# PA_Encoder.net
KiCad netlist of a schematic drawn in Altium Designer
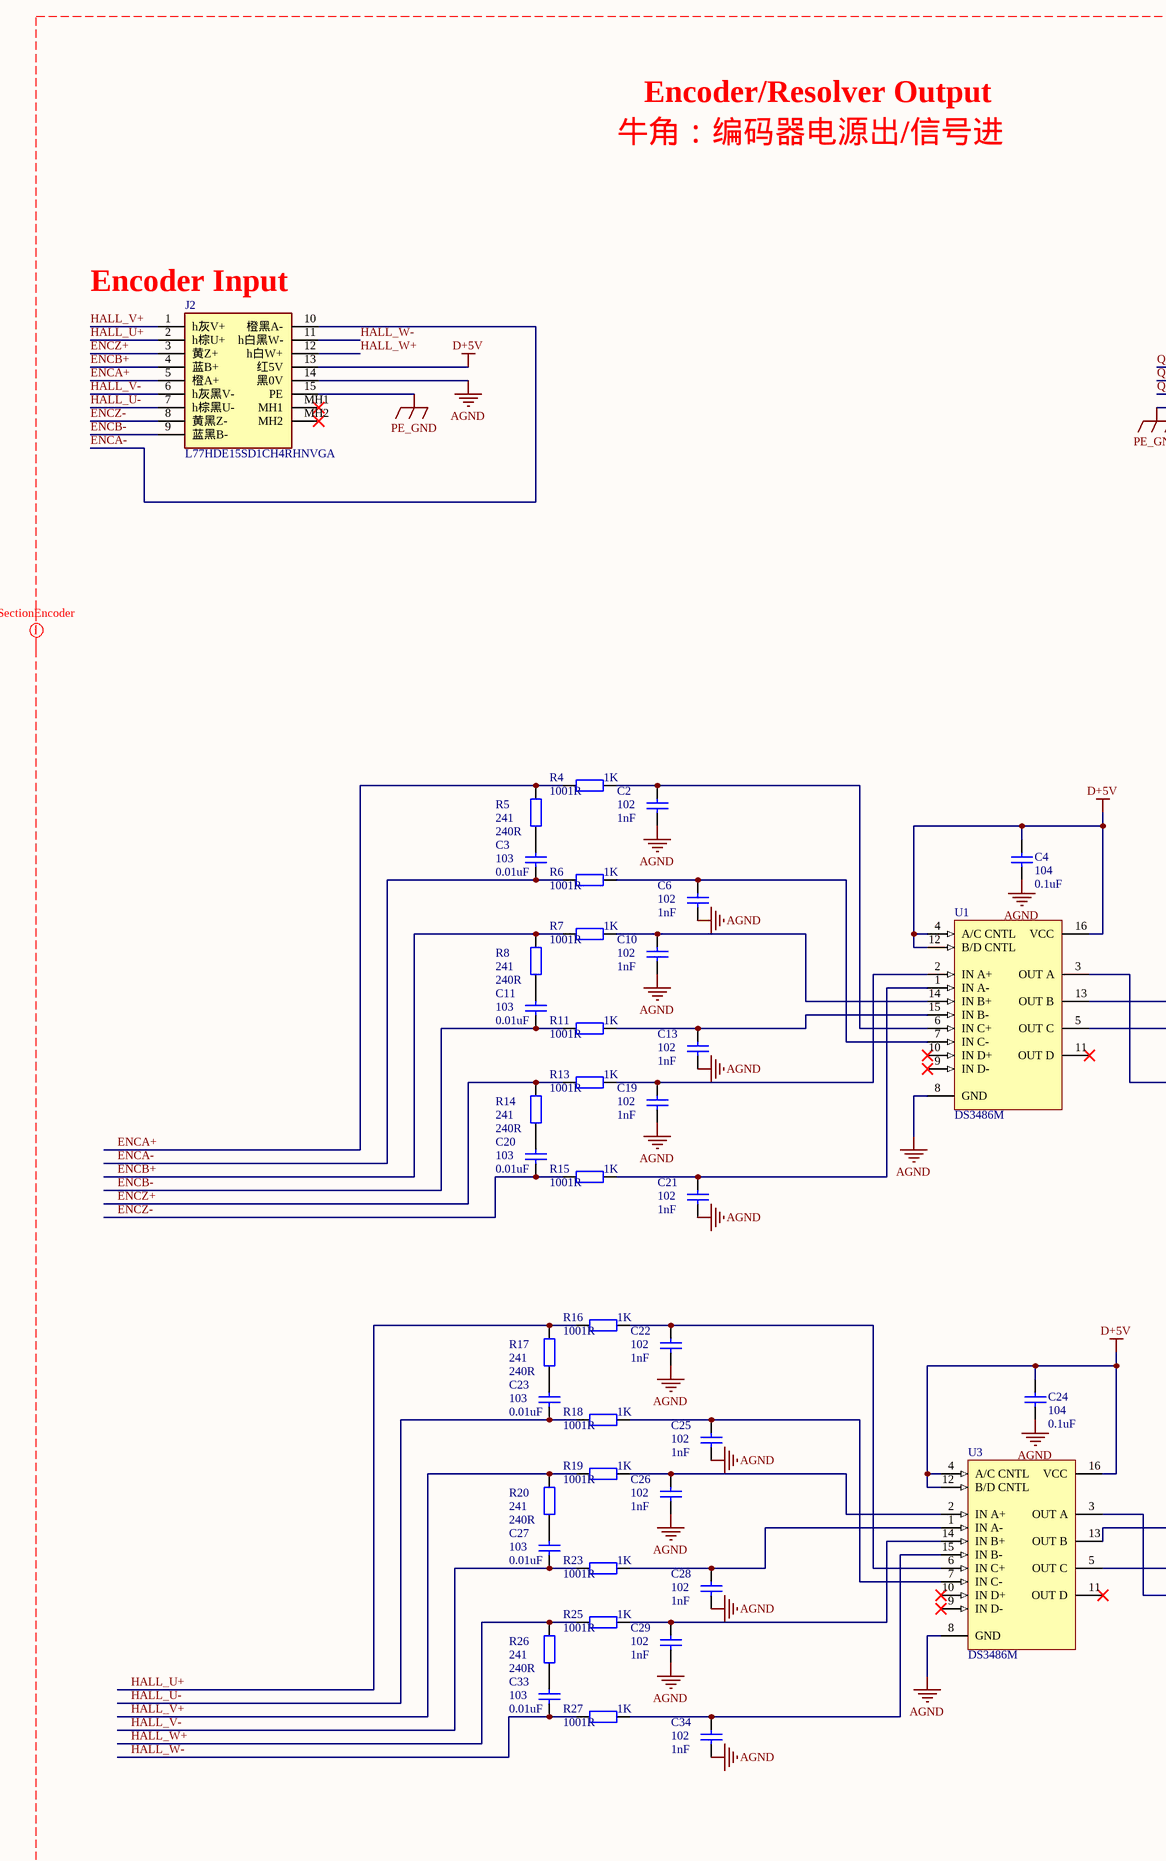
[diagram p0: PA_Encoder.SchDoc, left]
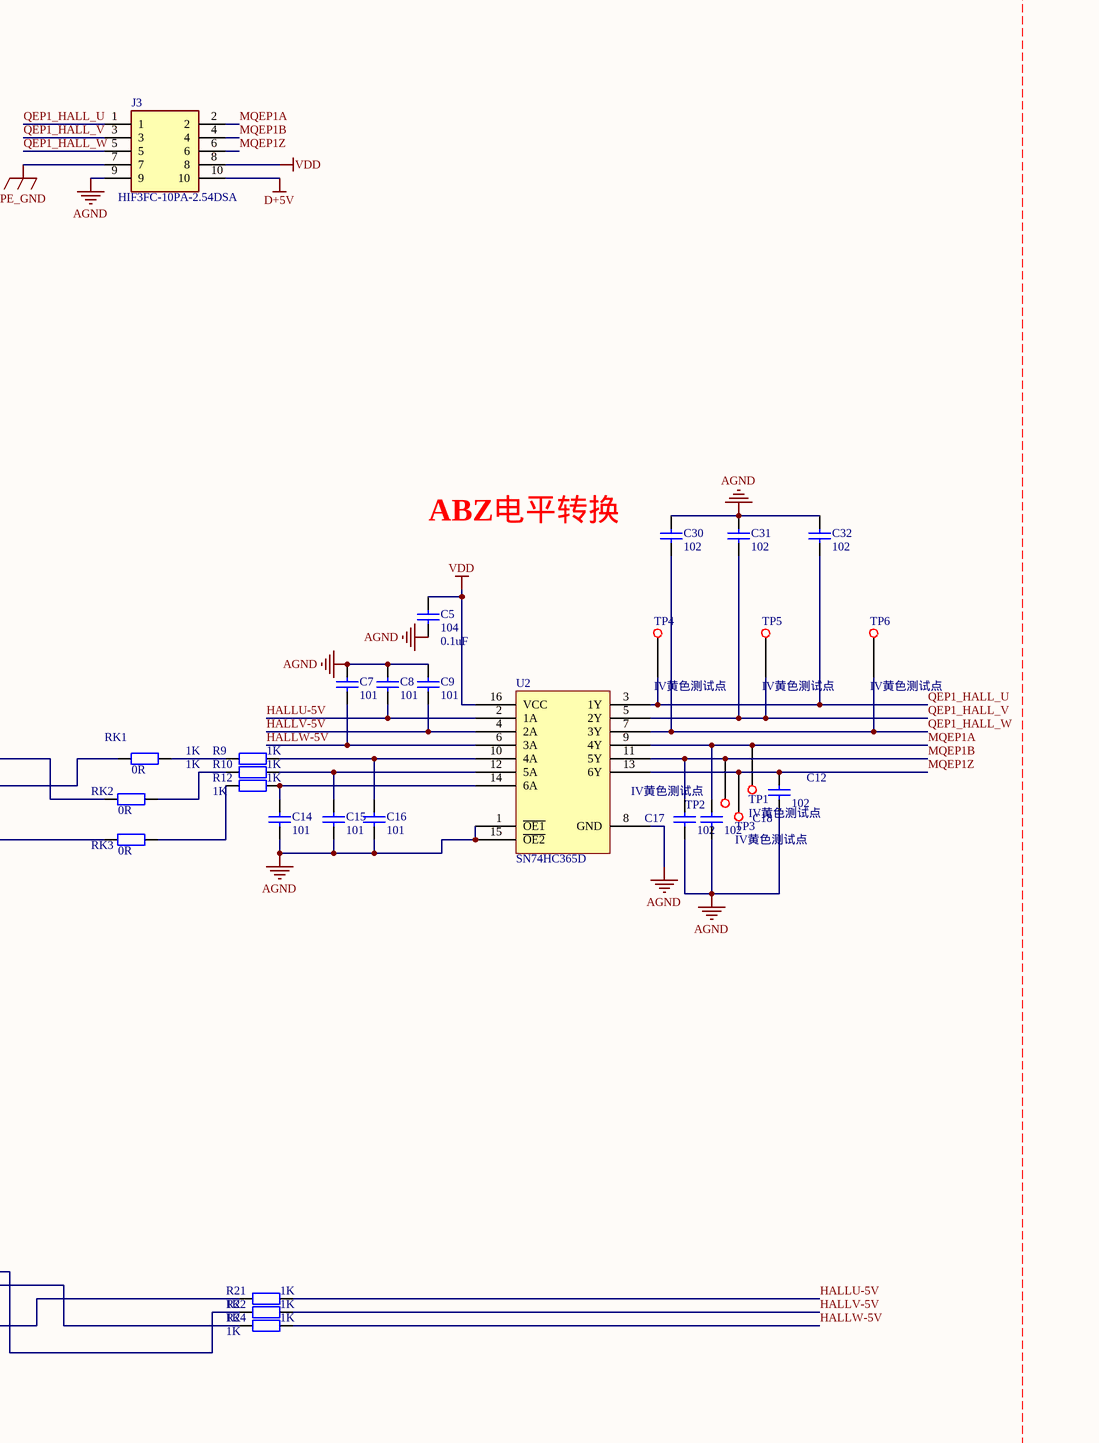
[diagram p1: PA_Encoder.SchDoc, middle]

(export (version "E")
  (design (tool "Eeschema 10.0.6"))
  (components
    (comp (ref "C2")
      (value "102")
      (footprint "0805")
      (description "Capacitor")
      (fields (field (name "ALTIUM_VALUE") "1nF") (field (name "PUBLISHER") "Altium Limited"))
      (libsource (lib "Miscellaneous Devices") (part "Cap"))
    )
    (comp (ref "C3")
      (value "103")
      (footprint "0805")
      (description "Capacitor")
      (fields (field (name "ALTIUM_VALUE") "0.01uF") (field (name "PUBLISHER") "Altium Limited"))
      (libsource (lib "Miscellaneous Devices") (part "Cap"))
    )
    (comp (ref "C4")
      (value "104")
      (footprint "0805")
      (description "Capacitor")
      (fields (field (name "ALTIUM_VALUE") "0.1uF") (field (name "PUBLISHER") "Altium Limited"))
      (libsource (lib "Miscellaneous Devices") (part "Cap"))
    )
    (comp (ref "C5")
      (value "104")
      (footprint "0805")
      (description "Capacitor")
      (fields (field (name "ALTIUM_VALUE") "0.1uF") (field (name "PUBLISHER") "Altium Limited"))
      (libsource (lib "Miscellaneous Devices") (part "Cap"))
    )
    (comp (ref "C6")
      (value "102")
      (footprint "0805")
      (description "Capacitor")
      (fields (field (name "ALTIUM_VALUE") "1nF") (field (name "PUBLISHER") "Altium Limited"))
      (libsource (lib "Miscellaneous Devices") (part "Cap"))
    )
    (comp (ref "C7")
      (value "101")
      (footprint "0805")
      (description "Capacitor")
      (fields (field (name "PUBLISHER") "Altium Limited"))
      (libsource (lib "Miscellaneous Devices") (part "Cap"))
    )
    (comp (ref "C8")
      (value "101")
      (footprint "0805")
      (description "Capacitor")
      (fields (field (name "PUBLISHER") "Altium Limited"))
      (libsource (lib "Miscellaneous Devices") (part "Cap"))
    )
    (comp (ref "C9")
      (value "101")
      (footprint "0805")
      (description "Capacitor")
      (fields (field (name "PUBLISHER") "Altium Limited"))
      (libsource (lib "Miscellaneous Devices") (part "Cap"))
    )
    (comp (ref "C10")
      (value "102")
      (footprint "0805")
      (description "Capacitor")
      (fields (field (name "ALTIUM_VALUE") "1nF") (field (name "PUBLISHER") "Altium Limited"))
      (libsource (lib "Miscellaneous Devices") (part "Cap"))
    )
    (comp (ref "C11")
      (value "103")
      (footprint "0805")
      (description "Capacitor")
      (fields (field (name "ALTIUM_VALUE") "0.01uF") (field (name "PUBLISHER") "Altium Limited"))
      (libsource (lib "Miscellaneous Devices") (part "Cap"))
    )
    (comp (ref "C12")
      (value "102")
      (footprint "0805")
      (description "Capacitor")
      (fields (field (name "PUBLISHER") "Altium Limited"))
      (libsource (lib "Miscellaneous Devices") (part "Cap"))
    )
    (comp (ref "C13")
      (value "102")
      (footprint "0805")
      (description "Capacitor")
      (fields (field (name "ALTIUM_VALUE") "1nF") (field (name "PUBLISHER") "Altium Limited"))
      (libsource (lib "Miscellaneous Devices") (part "Cap"))
    )
    (comp (ref "C14")
      (value "101")
      (footprint "0805")
      (description "Capacitor")
      (fields (field (name "PUBLISHER") "Altium Limited"))
      (libsource (lib "Miscellaneous Devices") (part "Cap"))
    )
    (comp (ref "C15")
      (value "101")
      (footprint "0805")
      (description "Capacitor")
      (fields (field (name "PUBLISHER") "Altium Limited"))
      (libsource (lib "Miscellaneous Devices") (part "Cap"))
    )
    (comp (ref "C16")
      (value "101")
      (footprint "0805")
      (description "Capacitor")
      (fields (field (name "PUBLISHER") "Altium Limited"))
      (libsource (lib "Miscellaneous Devices") (part "Cap"))
    )
    (comp (ref "C17")
      (value "102")
      (footprint "0805")
      (description "Capacitor")
      (fields (field (name "PUBLISHER") "Altium Limited"))
      (libsource (lib "Miscellaneous Devices") (part "Cap"))
    )
    (comp (ref "C18")
      (value "102")
      (footprint "0805")
      (description "Capacitor")
      (fields (field (name "PUBLISHER") "Altium Limited"))
      (libsource (lib "Miscellaneous Devices") (part "Cap"))
    )
    (comp (ref "C19")
      (value "102")
      (footprint "0805")
      (description "Capacitor")
      (fields (field (name "ALTIUM_VALUE") "1nF") (field (name "PUBLISHER") "Altium Limited"))
      (libsource (lib "Miscellaneous Devices") (part "Cap"))
    )
    (comp (ref "C20")
      (value "103")
      (footprint "0805")
      (description "Capacitor")
      (fields (field (name "ALTIUM_VALUE") "0.01uF") (field (name "PUBLISHER") "Altium Limited"))
      (libsource (lib "Miscellaneous Devices") (part "Cap"))
    )
    (comp (ref "C21")
      (value "102")
      (footprint "0805")
      (description "Capacitor")
      (fields (field (name "ALTIUM_VALUE") "1nF") (field (name "PUBLISHER") "Altium Limited"))
      (libsource (lib "Miscellaneous Devices") (part "Cap"))
    )
    (comp (ref "C22")
      (value "102")
      (footprint "0805")
      (description "Capacitor")
      (fields (field (name "ALTIUM_VALUE") "1nF") (field (name "PUBLISHER") "Altium Limited"))
      (libsource (lib "Miscellaneous Devices") (part "Cap"))
    )
    (comp (ref "C23")
      (value "103")
      (footprint "0805")
      (description "Capacitor")
      (fields (field (name "ALTIUM_VALUE") "0.01uF") (field (name "PUBLISHER") "Altium Limited"))
      (libsource (lib "Miscellaneous Devices") (part "Cap"))
    )
    (comp (ref "C24")
      (value "104")
      (footprint "0805")
      (description "Capacitor")
      (fields (field (name "ALTIUM_VALUE") "0.1uF") (field (name "PUBLISHER") "Altium Limited"))
      (libsource (lib "Miscellaneous Devices") (part "Cap"))
    )
    (comp (ref "C25")
      (value "102")
      (footprint "0805")
      (description "Capacitor")
      (fields (field (name "ALTIUM_VALUE") "1nF") (field (name "PUBLISHER") "Altium Limited"))
      (libsource (lib "Miscellaneous Devices") (part "Cap"))
    )
    (comp (ref "C26")
      (value "102")
      (footprint "0805")
      (description "Capacitor")
      (fields (field (name "ALTIUM_VALUE") "1nF") (field (name "PUBLISHER") "Altium Limited"))
      (libsource (lib "Miscellaneous Devices") (part "Cap"))
    )
    (comp (ref "C27")
      (value "103")
      (footprint "0805")
      (description "Capacitor")
      (fields (field (name "ALTIUM_VALUE") "0.01uF") (field (name "PUBLISHER") "Altium Limited"))
      (libsource (lib "Miscellaneous Devices") (part "Cap"))
    )
    (comp (ref "C28")
      (value "102")
      (footprint "0805")
      (description "Capacitor")
      (fields (field (name "ALTIUM_VALUE") "1nF") (field (name "PUBLISHER") "Altium Limited"))
      (libsource (lib "Miscellaneous Devices") (part "Cap"))
    )
    (comp (ref "C29")
      (value "102")
      (footprint "0805")
      (description "Capacitor")
      (fields (field (name "ALTIUM_VALUE") "1nF") (field (name "PUBLISHER") "Altium Limited"))
      (libsource (lib "Miscellaneous Devices") (part "Cap"))
    )
    (comp (ref "C30")
      (value "102")
      (footprint "0805")
      (description "Capacitor")
      (fields (field (name "PUBLISHER") "Altium Limited"))
      (libsource (lib "Miscellaneous Devices") (part "Cap"))
    )
    (comp (ref "C31")
      (value "102")
      (footprint "0805")
      (description "Capacitor")
      (fields (field (name "PUBLISHER") "Altium Limited"))
      (libsource (lib "Miscellaneous Devices") (part "Cap"))
    )
    (comp (ref "C32")
      (value "102")
      (footprint "0805")
      (description "Capacitor")
      (fields (field (name "PUBLISHER") "Altium Limited"))
      (libsource (lib "Miscellaneous Devices") (part "Cap"))
    )
    (comp (ref "C33")
      (value "103")
      (footprint "0805")
      (description "Capacitor")
      (fields (field (name "ALTIUM_VALUE") "0.01uF") (field (name "PUBLISHER") "Altium Limited"))
      (libsource (lib "Miscellaneous Devices") (part "Cap"))
    )
    (comp (ref "C34")
      (value "102")
      (footprint "0805")
      (description "Capacitor")
      (fields (field (name "ALTIUM_VALUE") "1nF") (field (name "PUBLISHER") "Altium Limited"))
      (libsource (lib "Miscellaneous Devices") (part "Cap"))
    )
    (comp (ref "J2")
      (value "L77HDE15SD1CH4RHNVGA")
      (footprint "L77hde15sd1ch4rhnvga")
      (description "Connector")
      (fields (field (name "MOUSER PART NUMBER") "523-7HDE15SDH4RHNVGA"))
      (libsource (lib "Project_Arsene") (part "VGA_母头_时代超群15线编码器定义"))
    )
    (comp (ref "J3")
      (value "HIF3FC-10PA-2.54DSA")
      (footprint "HIF3FC-10PA-2.54DSA")
      (description "Connector")
      (fields
        (field (name "MANUFACTURER_PART_NUMBER") "HIF3FC-10PA-2.54DSA(71)")
        (field (name "MOUSER PART NUMBER") "798-HIF3FC10PA254D71")
      )
      (libsource (lib "Project_Arsene") (part "HIF3FC-10PA-2.54DSA"))
    )
    (comp (ref "R4")
      (value "1001R")
      (footprint "0805")
      (description "Resistor")
      (fields (field (name "ALTIUM_VALUE") "1K") (field (name "PUBLISHER") "Altium Limited"))
      (libsource (lib "Miscellaneous Devices") (part "Res2"))
    )
    (comp (ref "R5")
      (value "241")
      (footprint "0805")
      (description "Resistor")
      (fields (field (name "ALTIUM_VALUE") "240R") (field (name "PUBLISHER") "Altium Limited"))
      (libsource (lib "") (part "Res2_1"))
    )
    (comp (ref "R6")
      (value "1001R")
      (footprint "0805")
      (description "Resistor")
      (fields (field (name "ALTIUM_VALUE") "1K") (field (name "PUBLISHER") "Altium Limited"))
      (libsource (lib "Miscellaneous Devices") (part "Res2"))
    )
    (comp (ref "R7")
      (value "1001R")
      (footprint "0805")
      (description "Resistor")
      (fields (field (name "ALTIUM_VALUE") "1K") (field (name "PUBLISHER") "Altium Limited"))
      (libsource (lib "Miscellaneous Devices") (part "Res2"))
    )
    (comp (ref "R8")
      (value "241")
      (footprint "0805")
      (description "Resistor")
      (fields (field (name "ALTIUM_VALUE") "240R") (field (name "PUBLISHER") "Altium Limited"))
      (libsource (lib "") (part "Res2_1"))
    )
    (comp (ref "R9")
      (value "1K")
      (footprint "0805")
      (description "Resistor")
      (fields (field (name "ALTIUM_VALUE") "1K") (field (name "PUBLISHER") "Altium Limited"))
      (libsource (lib "Miscellaneous Devices") (part "Res2"))
    )
    (comp (ref "R10")
      (value "1K")
      (footprint "0805")
      (description "Resistor")
      (fields (field (name "ALTIUM_VALUE") "1K") (field (name "PUBLISHER") "Altium Limited"))
      (libsource (lib "Miscellaneous Devices") (part "Res2"))
    )
    (comp (ref "R11")
      (value "1001R")
      (footprint "0805")
      (description "Resistor")
      (fields (field (name "ALTIUM_VALUE") "1K") (field (name "PUBLISHER") "Altium Limited"))
      (libsource (lib "Miscellaneous Devices") (part "Res2"))
    )
    (comp (ref "R12")
      (value "1K")
      (footprint "0805")
      (description "Resistor")
      (fields (field (name "ALTIUM_VALUE") "1K") (field (name "PUBLISHER") "Altium Limited"))
      (libsource (lib "Miscellaneous Devices") (part "Res2"))
    )
    (comp (ref "R13")
      (value "1001R")
      (footprint "0805")
      (description "Resistor")
      (fields (field (name "ALTIUM_VALUE") "1K") (field (name "PUBLISHER") "Altium Limited"))
      (libsource (lib "Miscellaneous Devices") (part "Res2"))
    )
    (comp (ref "R14")
      (value "241")
      (footprint "0805")
      (description "Resistor")
      (fields (field (name "ALTIUM_VALUE") "240R") (field (name "PUBLISHER") "Altium Limited"))
      (libsource (lib "") (part "Res2_1"))
    )
    (comp (ref "R15")
      (value "1001R")
      (footprint "0805")
      (description "Resistor")
      (fields (field (name "ALTIUM_VALUE") "1K") (field (name "PUBLISHER") "Altium Limited"))
      (libsource (lib "Miscellaneous Devices") (part "Res2"))
    )
    (comp (ref "R16")
      (value "1001R")
      (footprint "0805")
      (description "Resistor")
      (fields (field (name "ALTIUM_VALUE") "1K") (field (name "PUBLISHER") "Altium Limited"))
      (libsource (lib "Miscellaneous Devices") (part "Res2"))
    )
    (comp (ref "R17")
      (value "241")
      (footprint "0805")
      (description "Resistor")
      (fields (field (name "ALTIUM_VALUE") "240R") (field (name "PUBLISHER") "Altium Limited"))
      (libsource (lib "") (part "Res2_1"))
    )
    (comp (ref "R18")
      (value "1001R")
      (footprint "0805")
      (description "Resistor")
      (fields (field (name "ALTIUM_VALUE") "1K") (field (name "PUBLISHER") "Altium Limited"))
      (libsource (lib "Miscellaneous Devices") (part "Res2"))
    )
    (comp (ref "R19")
      (value "1001R")
      (footprint "0805")
      (description "Resistor")
      (fields (field (name "ALTIUM_VALUE") "1K") (field (name "PUBLISHER") "Altium Limited"))
      (libsource (lib "Miscellaneous Devices") (part "Res2"))
    )
    (comp (ref "R20")
      (value "241")
      (footprint "0805")
      (description "Resistor")
      (fields (field (name "ALTIUM_VALUE") "240R") (field (name "PUBLISHER") "Altium Limited"))
      (libsource (lib "") (part "Res2_1"))
    )
    (comp (ref "R21")
      (value "1K")
      (footprint "0805")
      (description "Resistor")
      (fields (field (name "ALTIUM_VALUE") "1K") (field (name "PUBLISHER") "Altium Limited"))
      (libsource (lib "Miscellaneous Devices") (part "Res2"))
    )
    (comp (ref "R22")
      (value "1K")
      (footprint "0805")
      (description "Resistor")
      (fields (field (name "ALTIUM_VALUE") "1K") (field (name "PUBLISHER") "Altium Limited"))
      (libsource (lib "Miscellaneous Devices") (part "Res2"))
    )
    (comp (ref "R23")
      (value "1001R")
      (footprint "0805")
      (description "Resistor")
      (fields (field (name "ALTIUM_VALUE") "1K") (field (name "PUBLISHER") "Altium Limited"))
      (libsource (lib "Miscellaneous Devices") (part "Res2"))
    )
    (comp (ref "R24")
      (value "1K")
      (footprint "0805")
      (description "Resistor")
      (fields (field (name "ALTIUM_VALUE") "1K") (field (name "PUBLISHER") "Altium Limited"))
      (libsource (lib "Miscellaneous Devices") (part "Res2"))
    )
    (comp (ref "R25")
      (value "1001R")
      (footprint "0805")
      (description "Resistor")
      (fields (field (name "ALTIUM_VALUE") "1K") (field (name "PUBLISHER") "Altium Limited"))
      (libsource (lib "Miscellaneous Devices") (part "Res2"))
    )
    (comp (ref "R26")
      (value "241")
      (footprint "0805")
      (description "Resistor")
      (fields (field (name "ALTIUM_VALUE") "240R") (field (name "PUBLISHER") "Altium Limited"))
      (libsource (lib "") (part "Res2_1"))
    )
    (comp (ref "R27")
      (value "1001R")
      (footprint "0805")
      (description "Resistor")
      (fields (field (name "ALTIUM_VALUE") "1K") (field (name "PUBLISHER") "Altium Limited"))
      (libsource (lib "Miscellaneous Devices") (part "Res2"))
    )
    (comp (ref "RK1")
      (value "0R")
      (footprint "0805")
      (description "Resistor")
      (fields (field (name "PUBLISHER") "Altium Limited"))
      (libsource (lib "Miscellaneous Devices") (part "Res2"))
    )
    (comp (ref "RK2")
      (value "0R")
      (footprint "0805")
      (description "Resistor")
      (fields (field (name "PUBLISHER") "Altium Limited"))
      (libsource (lib "Miscellaneous Devices") (part "Res2"))
    )
    (comp (ref "RK3")
      (value "0R")
      (footprint "0805")
      (description "Resistor")
      (fields (field (name "PUBLISHER") "Altium Limited"))
      (libsource (lib "Miscellaneous Devices") (part "Res2"))
    )
    (comp (ref "TP1") (value "IV黄色测试点") (footprint "TP") (libsource (lib "KING") (part "测试点")))
    (comp (ref "TP2") (value "IV黄色测试点") (footprint "TP") (libsource (lib "KING") (part "测试点")))
    (comp (ref "TP3") (value "IV黄色测试点") (footprint "TP") (libsource (lib "KING") (part "测试点")))
    (comp (ref "TP4") (value "IV黄色测试点") (footprint "TP") (libsource (lib "KING") (part "测试点")))
    (comp (ref "TP5") (value "IV黄色测试点") (footprint "TP") (libsource (lib "KING") (part "测试点")))
    (comp (ref "TP6") (value "IV黄色测试点") (footprint "TP") (libsource (lib "KING") (part "测试点")))
    (comp (ref "U1")
      (value "DS3486M")
      (footprint "M16A_N")
      (description "Quad RS-422, RS-423 Line Receiver")
      (fields (field (name "PUBLISHER") "Altium Limited"))
      (libsource (lib "NSC Interface Line Receiver") (part "DS3486M"))
    )
    (comp (ref "U2") (value "SN74HC365D") (footprint "D016_N") (libsource (lib "总库") (part "SN74HC365D")))
    (comp (ref "U3")
      (value "DS3486M")
      (footprint "M16A_N")
      (description "Quad RS-422, RS-423 Line Receiver")
      (fields (field (name "PUBLISHER") "Altium Limited"))
      (libsource (lib "NSC Interface Line Receiver") (part "DS3486M"))
    )
  )
  (nets
    (net (code "1") (name "/ENCA+") (class "Default")
      (node (ref "J2") (pin "5") (pinfunction "橙A+_5") (pintype "passive"))
      (node (ref "R4") (pin "1") (pinfunction "1_1") (pintype "passive"))
      (node (ref "R5") (pin "2") (pinfunction "2_2") (pintype "passive"))
    )
    (net (code "2") (name "/ENCA-") (class "Default")
      (node (ref "C3") (pin "1") (pinfunction "1_1") (pintype "passive"))
      (node (ref "J2") (pin "10") (pinfunction "橙黑A-_10") (pintype "passive"))
      (node (ref "R6") (pin "1") (pinfunction "1_1") (pintype "passive"))
    )
    (net (code "3") (name "/ENCB+") (class "Default")
      (node (ref "J2") (pin "4") (pinfunction "蓝B+_4") (pintype "passive"))
      (node (ref "R7") (pin "1") (pinfunction "1_1") (pintype "passive"))
      (node (ref "R8") (pin "2") (pinfunction "2_2") (pintype "passive"))
    )
    (net (code "4") (name "/ENCB-") (class "Default")
      (node (ref "C11") (pin "1") (pinfunction "1_1") (pintype "passive"))
      (node (ref "J2") (pin "9") (pinfunction "蓝黑B-_9") (pintype "passive"))
      (node (ref "R11") (pin "1") (pinfunction "1_1") (pintype "passive"))
    )
    (net (code "5") (name "/ENCZ+") (class "Default")
      (node (ref "J2") (pin "3") (pinfunction "黄Z+_3") (pintype "passive"))
      (node (ref "R13") (pin "1") (pinfunction "1_1") (pintype "passive"))
      (node (ref "R14") (pin "2") (pinfunction "2_2") (pintype "passive"))
    )
    (net (code "6") (name "/ENCZ-") (class "Default")
      (node (ref "C20") (pin "1") (pinfunction "1_1") (pintype "passive"))
      (node (ref "J2") (pin "8") (pinfunction "黄黑Z-_8") (pintype "passive"))
      (node (ref "R15") (pin "1") (pinfunction "1_1") (pintype "passive"))
    )
    (net (code "7") (name "/HALLU-5V") (class "Default")
      (node (ref "C8") (pin "2") (pinfunction "2_2") (pintype "passive"))
      (node (ref "R21") (pin "2") (pinfunction "2_2") (pintype "passive"))
      (node (ref "U2") (pin "2") (pinfunction "1A_2") (pintype "passive"))
    )
    (net (code "8") (name "/HALLV-5V") (class "Default")
      (node (ref "C9") (pin "2") (pinfunction "2_2") (pintype "passive"))
      (node (ref "R22") (pin "2") (pinfunction "2_2") (pintype "passive"))
      (node (ref "U2") (pin "4") (pinfunction "2A_4") (pintype "passive"))
    )
    (net (code "9") (name "/HALLW-5V") (class "Default")
      (node (ref "C7") (pin "2") (pinfunction "2_2") (pintype "passive"))
      (node (ref "R24") (pin "2") (pinfunction "2_2") (pintype "passive"))
      (node (ref "U2") (pin "6") (pinfunction "3A_6") (pintype "passive"))
    )
    (net (code "10") (name "/HALL_U+") (class "Default")
      (node (ref "J2") (pin "2") (pinfunction "h棕U+_2") (pintype "passive"))
      (node (ref "R16") (pin "1") (pinfunction "1_1") (pintype "passive"))
      (node (ref "R17") (pin "2") (pinfunction "2_2") (pintype "passive"))
    )
    (net (code "11") (name "/HALL_U-") (class "Default")
      (node (ref "C23") (pin "1") (pinfunction "1_1") (pintype "passive"))
      (node (ref "J2") (pin "7") (pinfunction "h棕黑U-_7") (pintype "passive"))
      (node (ref "R18") (pin "1") (pinfunction "1_1") (pintype "passive"))
    )
    (net (code "12") (name "/HALL_V+") (class "Default")
      (node (ref "J2") (pin "1") (pinfunction "h灰V+_1") (pintype "passive"))
      (node (ref "R19") (pin "1") (pinfunction "1_1") (pintype "passive"))
      (node (ref "R20") (pin "2") (pinfunction "2_2") (pintype "passive"))
    )
    (net (code "13") (name "/HALL_V-") (class "Default")
      (node (ref "C27") (pin "1") (pinfunction "1_1") (pintype "passive"))
      (node (ref "J2") (pin "6") (pinfunction "h灰黑V-_6") (pintype "passive"))
      (node (ref "R23") (pin "1") (pinfunction "1_1") (pintype "passive"))
    )
    (net (code "14") (name "/HALL_W+") (class "Default")
      (node (ref "J2") (pin "12") (pinfunction "h白W+_12") (pintype "passive"))
      (node (ref "R25") (pin "1") (pinfunction "1_1") (pintype "passive"))
      (node (ref "R26") (pin "2") (pinfunction "2_2") (pintype "passive"))
    )
    (net (code "15") (name "/HALL_W-") (class "Default")
      (node (ref "C33") (pin "1") (pinfunction "1_1") (pintype "passive"))
      (node (ref "J2") (pin "11") (pinfunction "h白黑W-_11") (pintype "passive"))
      (node (ref "R27") (pin "1") (pinfunction "1_1") (pintype "passive"))
    )
    (net (code "16") (name "/MQEP1A") (class "Default")
      (node (ref "C18") (pin "1") (pinfunction "1_1") (pintype "passive"))
      (node (ref "J3") (pin "2") (pinfunction "2_2") (pintype "passive"))
      (node (ref "TP1") (pin "1") (pintype "passive"))
      (node (ref "U2") (pin "9") (pinfunction "4Y_9") (pintype "passive"))
    )
    (net (code "17") (name "/MQEP1B") (class "Default")
      (node (ref "C17") (pin "1") (pinfunction "1_1") (pintype "passive"))
      (node (ref "J3") (pin "4") (pinfunction "4_4") (pintype "passive"))
      (node (ref "TP2") (pin "1") (pintype "passive"))
      (node (ref "U2") (pin "11") (pinfunction "5Y_11") (pintype "passive"))
    )
    (net (code "18") (name "/MQEP1Z") (class "Default")
      (node (ref "C12") (pin "1") (pinfunction "1_1") (pintype "passive"))
      (node (ref "J3") (pin "6") (pinfunction "6_6") (pintype "passive"))
      (node (ref "TP3") (pin "1") (pintype "passive"))
      (node (ref "U2") (pin "13") (pinfunction "6Y_13") (pintype "passive"))
    )
    (net (code "19") (name "/QEP1_HALL_U") (class "Default")
      (node (ref "C32") (pin "1") (pinfunction "1_1") (pintype "passive"))
      (node (ref "J3") (pin "1") (pinfunction "1_1") (pintype "passive"))
      (node (ref "TP4") (pin "1") (pintype "passive"))
      (node (ref "U2") (pin "3") (pinfunction "1Y_3") (pintype "passive"))
    )
    (net (code "20") (name "/QEP1_HALL_V") (class "Default")
      (node (ref "C31") (pin "1") (pinfunction "1_1") (pintype "passive"))
      (node (ref "J3") (pin "3") (pinfunction "3_3") (pintype "passive"))
      (node (ref "TP5") (pin "1") (pintype "passive"))
      (node (ref "U2") (pin "5") (pinfunction "2Y_5") (pintype "passive"))
    )
    (net (code "21") (name "/QEP1_HALL_W") (class "Default")
      (node (ref "C30") (pin "1") (pinfunction "1_1") (pintype "passive"))
      (node (ref "J3") (pin "5") (pinfunction "5_5") (pintype "passive"))
      (node (ref "TP6") (pin "1") (pintype "passive"))
      (node (ref "U2") (pin "7") (pinfunction "3Y_7") (pintype "passive"))
    )
    (net (code "22") (name "AGND") (class "Default")
      (node (ref "C10") (pin "1") (pinfunction "1_1") (pintype "passive"))
      (node (ref "C12") (pin "2") (pinfunction "2_2") (pintype "passive"))
      (node (ref "C13") (pin "1") (pinfunction "1_1") (pintype "passive"))
      (node (ref "C14") (pin "2") (pinfunction "2_2") (pintype "passive"))
      (node (ref "C15") (pin "2") (pinfunction "2_2") (pintype "passive"))
      (node (ref "C16") (pin "2") (pinfunction "2_2") (pintype "passive"))
      (node (ref "C17") (pin "2") (pinfunction "2_2") (pintype "passive"))
      (node (ref "C18") (pin "2") (pinfunction "2_2") (pintype "passive"))
      (node (ref "C19") (pin "1") (pinfunction "1_1") (pintype "passive"))
      (node (ref "C2") (pin "1") (pinfunction "1_1") (pintype "passive"))
      (node (ref "C21") (pin "1") (pinfunction "1_1") (pintype "passive"))
      (node (ref "C22") (pin "1") (pinfunction "1_1") (pintype "passive"))
      (node (ref "C24") (pin "1") (pinfunction "1_1") (pintype "passive"))
      (node (ref "C25") (pin "1") (pinfunction "1_1") (pintype "passive"))
      (node (ref "C26") (pin "1") (pinfunction "1_1") (pintype "passive"))
      (node (ref "C28") (pin "1") (pinfunction "1_1") (pintype "passive"))
      (node (ref "C29") (pin "1") (pinfunction "1_1") (pintype "passive"))
      (node (ref "C30") (pin "2") (pinfunction "2_2") (pintype "passive"))
      (node (ref "C31") (pin "2") (pinfunction "2_2") (pintype "passive"))
      (node (ref "C32") (pin "2") (pinfunction "2_2") (pintype "passive"))
      (node (ref "C34") (pin "1") (pinfunction "1_1") (pintype "passive"))
      (node (ref "C4") (pin "1") (pinfunction "1_1") (pintype "passive"))
      (node (ref "C5") (pin "2") (pinfunction "2_2") (pintype "passive"))
      (node (ref "C6") (pin "1") (pinfunction "1_1") (pintype "passive"))
      (node (ref "C7") (pin "1") (pinfunction "1_1") (pintype "passive"))
      (node (ref "C8") (pin "1") (pinfunction "1_1") (pintype "passive"))
      (node (ref "C9") (pin "1") (pinfunction "1_1") (pintype "passive"))
      (node (ref "J2") (pin "14") (pinfunction "黑0V_14") (pintype "passive"))
      (node (ref "J3") (pin "9") (pinfunction "9_9") (pintype "passive"))
      (node (ref "U1") (pin "8") (pinfunction "GND_8") (pintype "power_in"))
      (node (ref "U2") (pin "1") (pinfunction "~{OE1}_1") (pintype "passive"))
      (node (ref "U2") (pin "15") (pinfunction "~{OE2}_15") (pintype "passive"))
      (node (ref "U2") (pin "8") (pinfunction "GND_8") (pintype "passive"))
      (node (ref "U3") (pin "8") (pinfunction "GND_8") (pintype "power_in"))
    )
    (net (code "23") (name "D+5V") (class "Default")
      (node (ref "C24") (pin "2") (pinfunction "2_2") (pintype "passive"))
      (node (ref "C4") (pin "2") (pinfunction "2_2") (pintype "passive"))
      (node (ref "J2") (pin "13") (pinfunction "红5V_13") (pintype "passive"))
      (node (ref "J3") (pin "10") (pinfunction "10_10") (pintype "passive"))
      (node (ref "U1") (pin "12") (pinfunction "B/D_CNTL_12") (pintype "input"))
      (node (ref "U1") (pin "16") (pinfunction "VCC_16") (pintype "power_in"))
      (node (ref "U1") (pin "4") (pinfunction "A/C_CNTL_4") (pintype "input"))
      (node (ref "U3") (pin "12") (pinfunction "B/D_CNTL_12") (pintype "input"))
      (node (ref "U3") (pin "16") (pinfunction "VCC_16") (pintype "power_in"))
      (node (ref "U3") (pin "4") (pinfunction "A/C_CNTL_4") (pintype "input"))
    )
    (net (code "24") (name "Net-(C3-Pad2)") (class "Default")
      (node (ref "C3") (pin "2") (pinfunction "2_2") (pintype "passive"))
      (node (ref "R5") (pin "1") (pinfunction "1_1") (pintype "passive"))
    )
    (net (code "25") (name "Net-(C11-Pad2)") (class "Default")
      (node (ref "C11") (pin "2") (pinfunction "2_2") (pintype "passive"))
      (node (ref "R8") (pin "1") (pinfunction "1_1") (pintype "passive"))
    )
    (net (code "26") (name "Net-(C20-Pad2)") (class "Default")
      (node (ref "C20") (pin "2") (pinfunction "2_2") (pintype "passive"))
      (node (ref "R14") (pin "1") (pinfunction "1_1") (pintype "passive"))
    )
    (net (code "27") (name "Net-(C23-Pad2)") (class "Default")
      (node (ref "C23") (pin "2") (pinfunction "2_2") (pintype "passive"))
      (node (ref "R17") (pin "1") (pinfunction "1_1") (pintype "passive"))
    )
    (net (code "28") (name "Net-(C27-Pad2)") (class "Default")
      (node (ref "C27") (pin "2") (pinfunction "2_2") (pintype "passive"))
      (node (ref "R20") (pin "1") (pinfunction "1_1") (pintype "passive"))
    )
    (net (code "29") (name "Net-(C33-Pad2)") (class "Default")
      (node (ref "C33") (pin "2") (pinfunction "2_2") (pintype "passive"))
      (node (ref "R26") (pin "1") (pinfunction "1_1") (pintype "passive"))
    )
    (net (code "30") (name "Net-(R9-Pad1)") (class "Default")
      (node (ref "R9") (pin "1") (pinfunction "1_1") (pintype "passive"))
      (node (ref "RK1") (pin "2") (pinfunction "2_2") (pintype "passive"))
    )
    (net (code "31") (name "Net-(R10-Pad1)") (class "Default")
      (node (ref "R10") (pin "1") (pinfunction "1_1") (pintype "passive"))
      (node (ref "RK2") (pin "2") (pinfunction "2_2") (pintype "passive"))
    )
    (net (code "32") (name "Net-(R12-Pad1)") (class "Default")
      (node (ref "R12") (pin "1") (pinfunction "1_1") (pintype "passive"))
      (node (ref "RK3") (pin "2") (pinfunction "2_2") (pintype "passive"))
    )
    (net (code "33") (name "Net-(U1-IN_A+)") (class "Default")
      (node (ref "C19") (pin "2") (pinfunction "2_2") (pintype "passive"))
      (node (ref "R13") (pin "2") (pinfunction "2_2") (pintype "passive"))
      (node (ref "U1") (pin "2") (pinfunction "IN_A+_2") (pintype "input"))
    )
    (net (code "34") (name "Net-(U1-IN_A-)") (class "Default")
      (node (ref "C21") (pin "2") (pinfunction "2_2") (pintype "passive"))
      (node (ref "R15") (pin "2") (pinfunction "2_2") (pintype "passive"))
      (node (ref "U1") (pin "1") (pinfunction "IN_A-_1") (pintype "input"))
    )
    (net (code "35") (name "Net-(U1-IN_B+)") (class "Default")
      (node (ref "C10") (pin "2") (pinfunction "2_2") (pintype "passive"))
      (node (ref "R7") (pin "2") (pinfunction "2_2") (pintype "passive"))
      (node (ref "U1") (pin "14") (pinfunction "IN_B+_14") (pintype "input"))
    )
    (net (code "36") (name "Net-(U1-IN_B-)") (class "Default")
      (node (ref "C13") (pin "2") (pinfunction "2_2") (pintype "passive"))
      (node (ref "R11") (pin "2") (pinfunction "2_2") (pintype "passive"))
      (node (ref "U1") (pin "15") (pinfunction "IN_B-_15") (pintype "input"))
    )
    (net (code "37") (name "Net-(U1-IN_C+)") (class "Default")
      (node (ref "C2") (pin "2") (pinfunction "2_2") (pintype "passive"))
      (node (ref "R4") (pin "2") (pinfunction "2_2") (pintype "passive"))
      (node (ref "U1") (pin "6") (pinfunction "IN_C+_6") (pintype "input"))
    )
    (net (code "38") (name "Net-(U1-IN_C-)") (class "Default")
      (node (ref "C6") (pin "2") (pinfunction "2_2") (pintype "passive"))
      (node (ref "R6") (pin "2") (pinfunction "2_2") (pintype "passive"))
      (node (ref "U1") (pin "7") (pinfunction "IN_C-_7") (pintype "input"))
    )
    (net (code "39") (name "Net-(U1-OUT_A)") (class "Default")
      (node (ref "RK3") (pin "1") (pinfunction "1_1") (pintype "passive"))
      (node (ref "U1") (pin "3") (pinfunction "OUT_A_3") (pintype "tri_state"))
    )
    (net (code "40") (name "Net-(U1-OUT_B)") (class "Default")
      (node (ref "RK2") (pin "1") (pinfunction "1_1") (pintype "passive"))
      (node (ref "U1") (pin "13") (pinfunction "OUT_B_13") (pintype "tri_state"))
    )
    (net (code "41") (name "Net-(U1-OUT_C)") (class "Default")
      (node (ref "RK1") (pin "1") (pinfunction "1_1") (pintype "passive"))
      (node (ref "U1") (pin "5") (pinfunction "OUT_C_5") (pintype "tri_state"))
    )
    (net (code "42") (name "Net-(U2-4A)") (class "Default")
      (node (ref "C16") (pin "1") (pinfunction "1_1") (pintype "passive"))
      (node (ref "R9") (pin "2") (pinfunction "2_2") (pintype "passive"))
      (node (ref "U2") (pin "10") (pinfunction "4A_10") (pintype "passive"))
    )
    (net (code "43") (name "Net-(U2-5A)") (class "Default")
      (node (ref "C15") (pin "1") (pinfunction "1_1") (pintype "passive"))
      (node (ref "R10") (pin "2") (pinfunction "2_2") (pintype "passive"))
      (node (ref "U2") (pin "12") (pinfunction "5A_12") (pintype "passive"))
    )
    (net (code "44") (name "Net-(U2-6A)") (class "Default")
      (node (ref "C14") (pin "1") (pinfunction "1_1") (pintype "passive"))
      (node (ref "R12") (pin "2") (pinfunction "2_2") (pintype "passive"))
      (node (ref "U2") (pin "14") (pinfunction "6A_14") (pintype "passive"))
    )
    (net (code "45") (name "Net-(U3-IN_A+)") (class "Default")
      (node (ref "C26") (pin "2") (pinfunction "2_2") (pintype "passive"))
      (node (ref "R19") (pin "2") (pinfunction "2_2") (pintype "passive"))
      (node (ref "U3") (pin "2") (pinfunction "IN_A+_2") (pintype "input"))
    )
    (net (code "46") (name "Net-(U3-IN_A-)") (class "Default")
      (node (ref "C28") (pin "2") (pinfunction "2_2") (pintype "passive"))
      (node (ref "R23") (pin "2") (pinfunction "2_2") (pintype "passive"))
      (node (ref "U3") (pin "1") (pinfunction "IN_A-_1") (pintype "input"))
    )
    (net (code "47") (name "Net-(U3-IN_B+)") (class "Default")
      (node (ref "C29") (pin "2") (pinfunction "2_2") (pintype "passive"))
      (node (ref "R25") (pin "2") (pinfunction "2_2") (pintype "passive"))
      (node (ref "U3") (pin "14") (pinfunction "IN_B+_14") (pintype "input"))
    )
    (net (code "48") (name "Net-(U3-IN_B-)") (class "Default")
      (node (ref "C34") (pin "2") (pinfunction "2_2") (pintype "passive"))
      (node (ref "R27") (pin "2") (pinfunction "2_2") (pintype "passive"))
      (node (ref "U3") (pin "15") (pinfunction "IN_B-_15") (pintype "input"))
    )
    (net (code "49") (name "Net-(U3-IN_C+)") (class "Default")
      (node (ref "C22") (pin "2") (pinfunction "2_2") (pintype "passive"))
      (node (ref "R16") (pin "2") (pinfunction "2_2") (pintype "passive"))
      (node (ref "U3") (pin "6") (pinfunction "IN_C+_6") (pintype "input"))
    )
    (net (code "50") (name "Net-(U3-IN_C-)") (class "Default")
      (node (ref "C25") (pin "2") (pinfunction "2_2") (pintype "passive"))
      (node (ref "R18") (pin "2") (pinfunction "2_2") (pintype "passive"))
      (node (ref "U3") (pin "7") (pinfunction "IN_C-_7") (pintype "input"))
    )
    (net (code "51") (name "Net-(U3-OUT_A)") (class "Default")
      (node (ref "R22") (pin "1") (pinfunction "1_1") (pintype "passive"))
      (node (ref "U3") (pin "3") (pinfunction "OUT_A_3") (pintype "tri_state"))
    )
    (net (code "52") (name "Net-(U3-OUT_B)") (class "Default")
      (node (ref "R24") (pin "1") (pinfunction "1_1") (pintype "passive"))
      (node (ref "U3") (pin "13") (pinfunction "OUT_B_13") (pintype "tri_state"))
    )
    (net (code "53") (name "Net-(U3-OUT_C)") (class "Default")
      (node (ref "R21") (pin "1") (pinfunction "1_1") (pintype "passive"))
      (node (ref "U3") (pin "5") (pinfunction "OUT_C_5") (pintype "tri_state"))
    )
    (net (code "54") (name "PE_GND") (class "Default")
      (node (ref "J2") (pin "15") (pinfunction "PE_15") (pintype "passive"))
      (node (ref "J3") (pin "7") (pinfunction "7_7") (pintype "passive"))
    )
    (net (code "55") (name "VDD") (class "Default")
      (node (ref "C5") (pin "1") (pinfunction "1_1") (pintype "passive"))
      (node (ref "J3") (pin "8") (pinfunction "8_8") (pintype "passive"))
      (node (ref "U2") (pin "16") (pinfunction "VCC_16") (pintype "passive"))
    )
    (net (code "56") (name "unconnected-(J2-PadMH1)") (class "Default")
      (node (ref "J2") (pin "MH1") (pinfunction "MH1_MH1") (pintype "passive+no_connect"))
    )
    (net (code "57") (name "unconnected-(J2-PadMH2)") (class "Default")
      (node (ref "J2") (pin "MH2") (pinfunction "MH2_MH2") (pintype "passive+no_connect"))
    )
    (net (code "58") (name "unconnected-(U1-IN_D+-Pad10)") (class "Default")
      (node (ref "U1") (pin "10") (pinfunction "IN_D+_10") (pintype "input+no_connect"))
    )
    (net (code "59") (name "unconnected-(U1-IN_D--Pad9)") (class "Default")
      (node (ref "U1") (pin "9") (pinfunction "IN_D-_9") (pintype "input+no_connect"))
    )
    (net (code "60") (name "unconnected-(U1-OUT_D-Pad11)") (class "Default")
      (node (ref "U1") (pin "11") (pinfunction "OUT_D_11") (pintype "tri_state+no_connect"))
    )
    (net (code "61") (name "unconnected-(U3-IN_D+-Pad10)") (class "Default")
      (node (ref "U3") (pin "10") (pinfunction "IN_D+_10") (pintype "input+no_connect"))
    )
    (net (code "62") (name "unconnected-(U3-IN_D--Pad9)") (class "Default")
      (node (ref "U3") (pin "9") (pinfunction "IN_D-_9") (pintype "input+no_connect"))
    )
    (net (code "63") (name "unconnected-(U3-OUT_D-Pad11)") (class "Default")
      (node (ref "U3") (pin "11") (pinfunction "OUT_D_11") (pintype "tri_state+no_connect"))
    )
  )
)
